# Liq_Power.net
KiCad netlist of a schematic drawn in Altium Designer
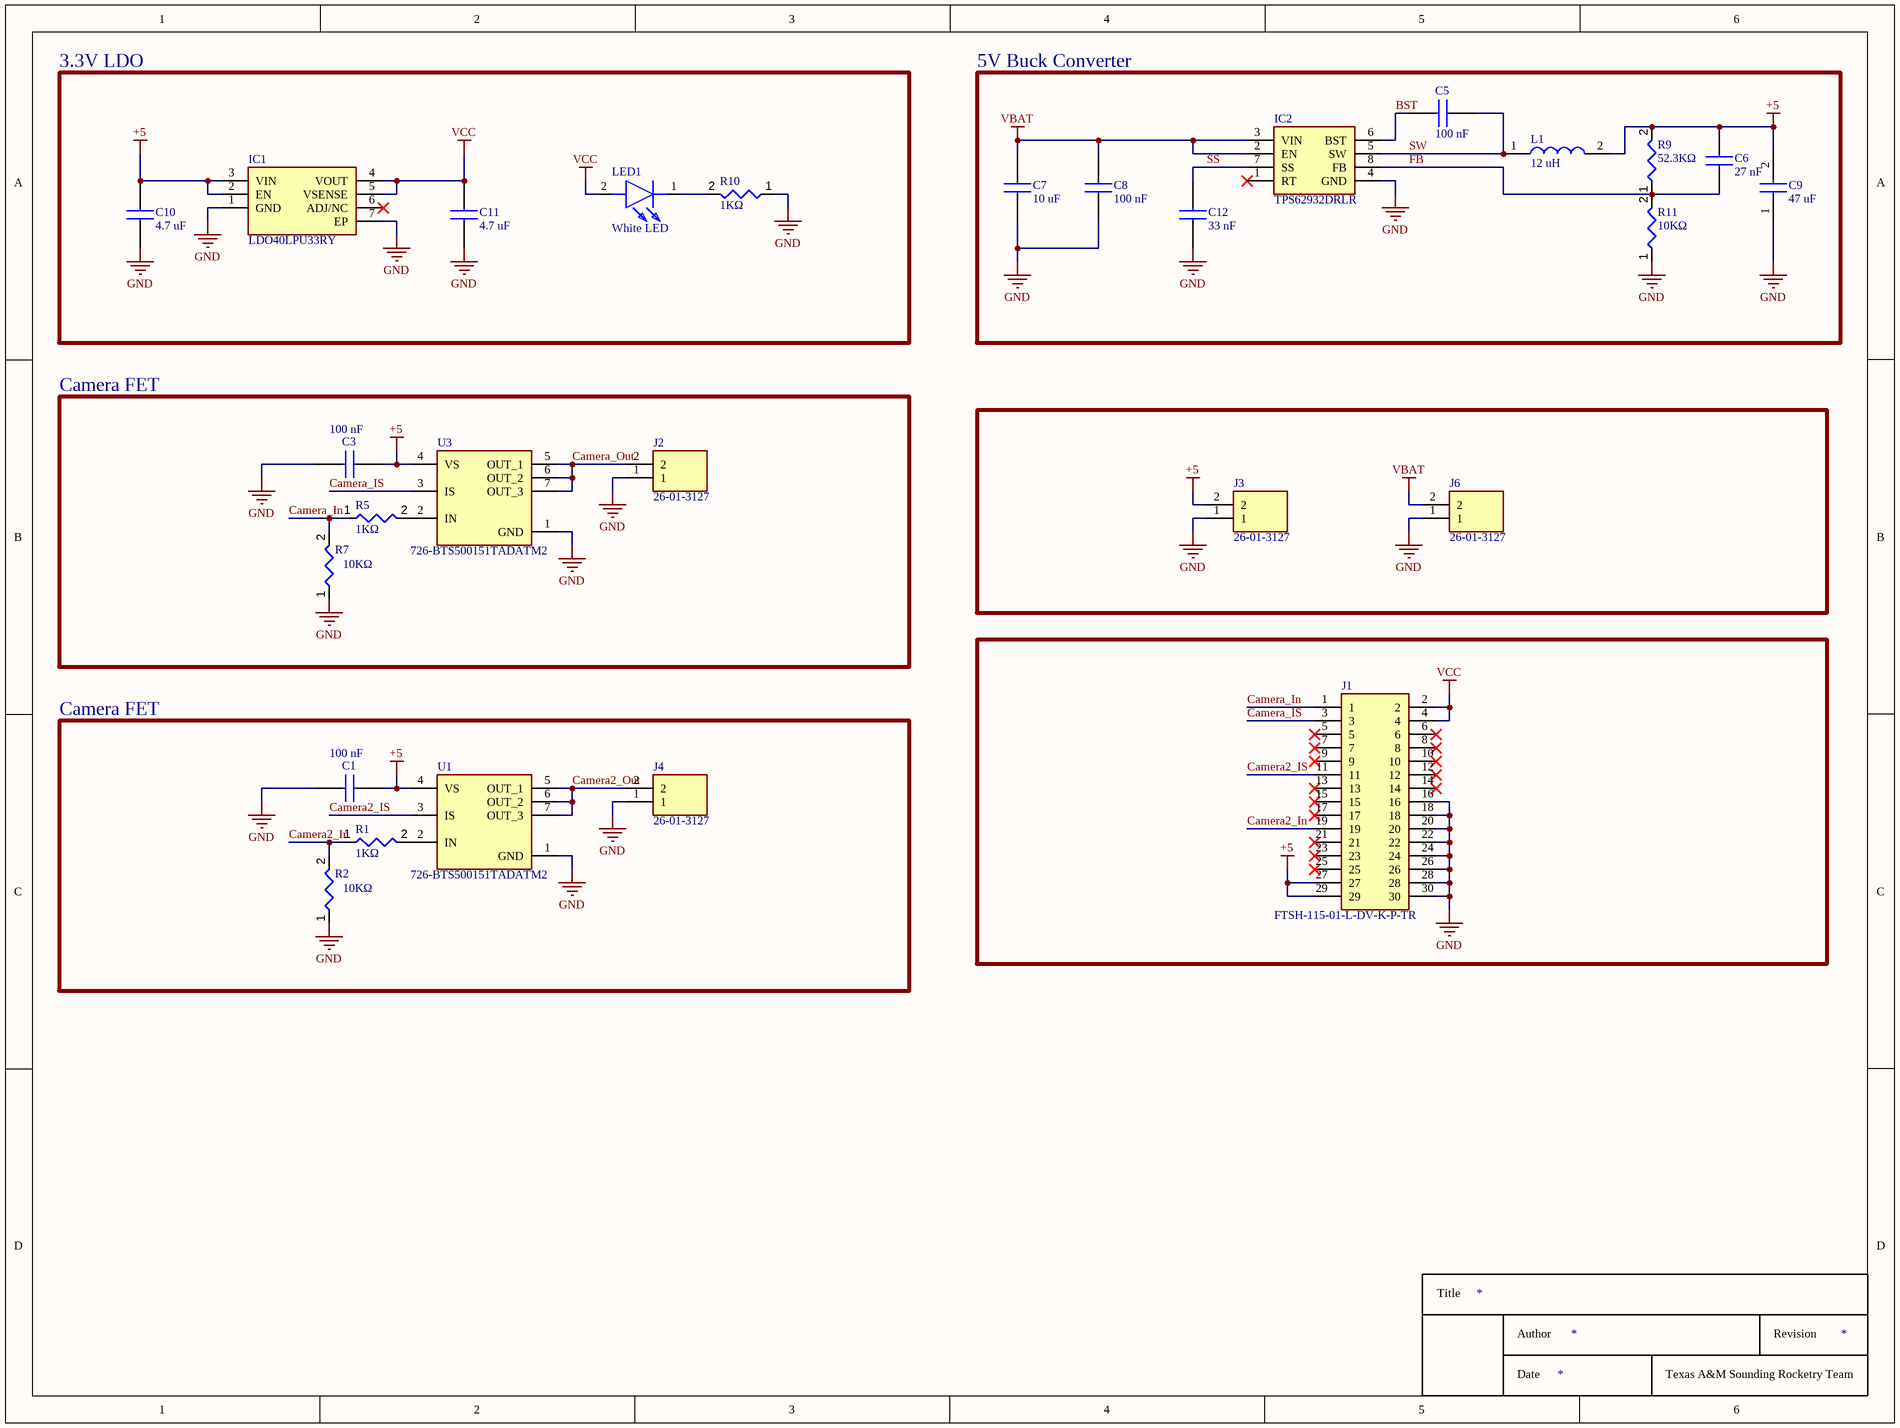
[diagram p0: Liq_Power.SchDoc]

(export (version "E")
  (design (tool "Eeschema 10.0.6"))
  (components
    (comp (ref "C1")
      (value "100 nF")
      (footprint "CAP_0603")
      (fields (field (name "TOLERANCE") "5%") (field (name "VOLTAGE") "50 V"))
      (libsource (lib "Capacitors") (part "Capacitor_BASE"))
    )
    (comp (ref "C3")
      (value "100 nF")
      (footprint "CAP_0603")
      (fields (field (name "TOLERANCE") "5%") (field (name "VOLTAGE") "50 V"))
      (libsource (lib "Capacitors") (part "Capacitor_BASE"))
    )
    (comp (ref "C5")
      (value "100 nF")
      (footprint "CAP_0603")
      (fields (field (name "TOLERANCE") "5%") (field (name "VOLTAGE") "50 V"))
      (libsource (lib "Capacitors") (part "Capacitor_BASE"))
    )
    (comp (ref "C6")
      (value "27 nF")
      (footprint "CAP_0603")
      (fields
        (field (name "TOLERANCE") "5%")
        (field (name "VOLTAGE") "50 V")
        (field (name "MPN") "581-06035C273JAT2A")
      )
      (libsource (lib "Capacitors") (part "Capacitor_BASE"))
    )
    (comp (ref "C7")
      (value "10 uF")
      (footprint "CAP_0603")
      (fields (field (name "TOLERANCE") "10%") (field (name "VOLTAGE") "25 V"))
      (libsource (lib "Capacitors") (part "Capacitor_BASE"))
    )
    (comp (ref "C8")
      (value "100 nF")
      (footprint "CAP_0603")
      (fields (field (name "TOLERANCE") "5%") (field (name "VOLTAGE") "50 V"))
      (libsource (lib "Capacitors") (part "Capacitor_BASE"))
    )
    (comp (ref "C9")
      (value "47 uF")
      (footprint "Capacitors:CAPC2012X145N")
      (description "KGM21AR51A476MU\r\n20% 10V")
      (fields
        (field (name "MANUFACTURER_PART_NUMBER") "KGM21AR51A476MU")
        (field (name "MOUSER PART NUMBER") "581-KGM21AR51A476MU")
      )
      (libsource (lib "Capacitors") (part "47 uF"))
    )
    (comp (ref "C10")
      (value "4.7 uF")
      (footprint "CAP_0603")
      (fields
        (field (name "TOLERANCE") "10%")
        (field (name "VOLTAGE") "25 V")
        (field (name "MPN") "581-06033D475KAT2A")
      )
      (libsource (lib "Capacitors") (part "Capacitor_BASE"))
    )
    (comp (ref "C11")
      (value "4.7 uF")
      (footprint "CAP_0603")
      (fields
        (field (name "TOLERANCE") "10%")
        (field (name "VOLTAGE") "25 V")
        (field (name "MPN") "581-06033D475KAT2A")
      )
      (libsource (lib "Capacitors") (part "Capacitor_BASE"))
    )
    (comp (ref "C12")
      (value "33 nF")
      (footprint "CAP_0603")
      (fields (field (name "TOLERANCE") "5%") (field (name "VOLTAGE") "50 V"))
      (libsource (lib "Capacitors") (part "Capacitor_BASE"))
    )
    (comp (ref "IC1")
      (value "LDO40LPU33RY")
      (footprint "Miscellaneous:SON95P300X300X90-7N-D")
      (description "3.3V 400 mA LDO")
      (fields (field (name "MOUSER PART NUMBER") "511-LDO40LPU33RY"))
      (libsource (lib "Miscellaneous") (part "LDO40LPU33RY"))
    )
    (comp (ref "IC2")
      (value "TPS62932DRLR")
      (footprint "Miscellaneous:TPS62932DRLR")
      (description "Integrated Circuit")
      (fields (field (name "MOUSER PART NUMBER") "595-TPS62932DRLR"))
      (libsource (lib "Miscellaneous") (part "TPS62932DRLR"))
    )
    (comp (ref "J1")
      (value "FTSH-115-01-L-DV-K-P-TR")
      (footprint "Connectors:FTSH-115-XX-YYY-DV-K-P-TR")
      (description "2x15 Board to Board")
      (fields (field (name "MOUSER PART NUMBER") "200-FTSH11501LDVKPTR"))
      (libsource (lib "Connectors") (part "FTSH-115-01-L-DV-K-P-TR"))
    )
    (comp (ref "J2")
      (value "26-01-3127")
      (footprint "SamacSys:26013127")
      (description "Connector")
      (fields (field (name "MOUSER PART NUMBER") "538-26-01-3127"))
      (libsource (lib "*") (part "26-01-3127"))
    )
    (comp (ref "J3")
      (value "26-01-3127")
      (footprint "SamacSys:26013127")
      (description "Connector")
      (fields (field (name "MOUSER PART NUMBER") "538-26-01-3127"))
      (libsource (lib "*") (part "26-01-3127"))
    )
    (comp (ref "J4")
      (value "26-01-3127")
      (footprint "SamacSys:26013127")
      (description "Connector")
      (fields (field (name "MOUSER PART NUMBER") "538-26-01-3127"))
      (libsource (lib "*") (part "26-01-3127"))
    )
    (comp (ref "J6")
      (value "26-01-3127")
      (footprint "SamacSys:26013127")
      (description "Connector")
      (fields (field (name "MOUSER PART NUMBER") "538-26-01-3127"))
      (libsource (lib "*") (part "26-01-3127"))
    )
    (comp (ref "L1")
      (value "12 uH")
      (footprint "Inductors:INDPM127127X850N")
      (description "SRR1208-120ML\r\n25 mOhm 20%")
      (fields
        (field (name "MANUFACTURER_PART_NUMBER") "SRR1208-120ML")
        (field (name "MOUSER PART NUMBER") "652-SRR1208-120ML")
      )
      (libsource (lib "Inductors") (part "12 uH"))
    )
    (comp (ref "LED1")
      (value "White LED")
      (footprint "Diodes:LEDC2012X90N")
      (description "LED")
      (fields
        (field (name "MANUFACTURER_PART_NUMBER") "HSMW-C170-U0000")
        (field (name "MPN") "630-HSMW-C170-U0000")
      )
      (libsource (lib "Diodes") (part "White LED"))
    )
    (comp (ref "R1")
      (value "1KΩ")
      (footprint "RES_0603")
      (description "Thick Film Resistors - SMD General Purpose Chip Resistor 0603, 1kOhms, 1%, 1/10W")
      (fields (field (name "TOLERANCE") "0.01") (field (name "POWER") "0.1W"))
      (libsource (lib "Resistors") (part "Resistor_BASE"))
    )
    (comp (ref "R2")
      (value "10KΩ")
      (footprint "RES_0603")
      (description "Thick Film Resistors - SMD General Purpose Chip Resistor 0603, 10kOhms, 1%, 1/10W")
      (fields (field (name "TOLERANCE") "0.01") (field (name "POWER") "0.1W"))
      (libsource (lib "Resistors") (part "Resistor_BASE"))
    )
    (comp (ref "R5")
      (value "1KΩ")
      (footprint "RES_0603")
      (description "Thick Film Resistors - SMD General Purpose Chip Resistor 0603, 1kOhms, 1%, 1/10W")
      (fields (field (name "TOLERANCE") "0.01") (field (name "POWER") "0.1W"))
      (libsource (lib "Resistors") (part "Resistor_BASE"))
    )
    (comp (ref "R7")
      (value "10KΩ")
      (footprint "RES_0603")
      (description "Thick Film Resistors - SMD General Purpose Chip Resistor 0603, 10kOhms, 1%, 1/10W")
      (fields (field (name "TOLERANCE") "0.01") (field (name "POWER") "0.1W"))
      (libsource (lib "Resistors") (part "Resistor_BASE"))
    )
    (comp (ref "R9")
      (value "52.3KΩ")
      (footprint "RES_0603")
      (description "Thick Film Resistors - SMD General Purpose Chip Resistor 0603, 52.3kOhms, 1%, 1/10W")
      (fields (field (name "TOLERANCE") "0.01") (field (name "POWER") "0.1W"))
      (libsource (lib "Resistors") (part "Resistor_BASE"))
    )
    (comp (ref "R10")
      (value "1KΩ")
      (footprint "RES_0603")
      (description "Thick Film Resistors - SMD General Purpose Chip Resistor 0603, 1kOhms, 1%, 1/10W")
      (fields (field (name "TOLERANCE") "0.01") (field (name "POWER") "0.1W"))
      (libsource (lib "Resistors") (part "Resistor_BASE"))
    )
    (comp (ref "R11")
      (value "10KΩ")
      (footprint "RES_0603")
      (description "Thick Film Resistors - SMD General Purpose Chip Resistor 0603, 10kOhms, 1%, 1/10W")
      (fields (field (name "TOLERANCE") "0.01") (field (name "POWER") "0.1W"))
      (libsource (lib "Resistors") (part "Resistor_BASE"))
    )
    (comp (ref "U1")
      (value "726-BTS500151TADATM2")
      (footprint "Transistors:BTS500151TADATMA2")
      (description "High-Side Switch 33 A")
      (fields
        (field (name "MANUFACTURER") "Infineon Technologies")
        (field (name "MANUFACTURER PART NUMBER") "BTS500151TADATMA2")
      )
      (libsource (lib "Transistors") (part "BTS500151TADATMA2"))
    )
    (comp (ref "U3")
      (value "726-BTS500151TADATM2")
      (footprint "Transistors:BTS500151TADATMA2")
      (description "High-Side Switch 33 A")
      (fields
        (field (name "MANUFACTURER") "Infineon Technologies")
        (field (name "MANUFACTURER PART NUMBER") "BTS500151TADATMA2")
      )
      (libsource (lib "Transistors") (part "BTS500151TADATMA2"))
    )
  )
  (nets
    (net (code "1") (name "+5") (class "Default")
      (node (ref "C1") (pin "1") (pinfunction "1_1") (pintype "passive"))
      (node (ref "C10") (pin "2") (pinfunction "2_2") (pintype "passive"))
      (node (ref "C3") (pin "1") (pinfunction "1_1") (pintype "passive"))
      (node (ref "C6") (pin "2") (pinfunction "2_2") (pintype "passive"))
      (node (ref "C9") (pin "2") (pinfunction "2_2") (pintype "passive"))
      (node (ref "IC1") (pin "2") (pinfunction "EN_2") (pintype "passive"))
      (node (ref "IC1") (pin "3") (pinfunction "VIN_3") (pintype "passive"))
      (node (ref "J1") (pin "27") (pinfunction "27_27") (pintype "passive"))
      (node (ref "J1") (pin "29") (pinfunction "29_29") (pintype "passive"))
      (node (ref "J3") (pin "2") (pinfunction "2_2") (pintype "passive"))
      (node (ref "L1") (pin "2") (pinfunction "2_2") (pintype "passive"))
      (node (ref "R9") (pin "2") (pinfunction "2_2") (pintype "passive"))
      (node (ref "U1") (pin "4") (pinfunction "VS_4") (pintype "passive"))
      (node (ref "U3") (pin "4") (pinfunction "VS_4") (pintype "passive"))
    )
    (net (code "2") (name "/BST") (class "Default")
      (node (ref "C5") (pin "1") (pinfunction "1_1") (pintype "passive"))
      (node (ref "IC2") (pin "6") (pinfunction "BST_6") (pintype "passive"))
    )
    (net (code "3") (name "/Camera2_IS") (class "Default")
      (node (ref "J1") (pin "11") (pinfunction "11_11") (pintype "passive"))
      (node (ref "U1") (pin "3") (pinfunction "IS_3") (pintype "passive"))
    )
    (net (code "4") (name "/Camera2_In") (class "Default")
      (node (ref "J1") (pin "19") (pinfunction "19_19") (pintype "passive"))
      (node (ref "R1") (pin "1") (pinfunction "1_1") (pintype "passive"))
      (node (ref "R2") (pin "2") (pinfunction "2_2") (pintype "passive"))
    )
    (net (code "5") (name "/Camera2_Out") (class "Default")
      (node (ref "J4") (pin "2") (pinfunction "2_2") (pintype "passive"))
      (node (ref "U1") (pin "5") (pinfunction "OUT_1_5") (pintype "passive"))
      (node (ref "U1") (pin "6") (pinfunction "OUT_2_6") (pintype "passive"))
      (node (ref "U1") (pin "7") (pinfunction "OUT_3_7") (pintype "passive"))
    )
    (net (code "6") (name "/Camera_IS") (class "Default")
      (node (ref "J1") (pin "3") (pinfunction "3_3") (pintype "passive"))
      (node (ref "U3") (pin "3") (pinfunction "IS_3") (pintype "passive"))
    )
    (net (code "7") (name "/Camera_In") (class "Default")
      (node (ref "J1") (pin "1") (pinfunction "1_1") (pintype "passive"))
      (node (ref "R5") (pin "1") (pinfunction "1_1") (pintype "passive"))
      (node (ref "R7") (pin "2") (pinfunction "2_2") (pintype "passive"))
    )
    (net (code "8") (name "/Camera_Out") (class "Default")
      (node (ref "J2") (pin "2") (pinfunction "2_2") (pintype "passive"))
      (node (ref "U3") (pin "5") (pinfunction "OUT_1_5") (pintype "passive"))
      (node (ref "U3") (pin "6") (pinfunction "OUT_2_6") (pintype "passive"))
      (node (ref "U3") (pin "7") (pinfunction "OUT_3_7") (pintype "passive"))
    )
    (net (code "9") (name "/FB") (class "Default")
      (node (ref "C6") (pin "1") (pinfunction "1_1") (pintype "passive"))
      (node (ref "IC2") (pin "8") (pinfunction "FB_8") (pintype "passive"))
      (node (ref "R11") (pin "2") (pinfunction "2_2") (pintype "passive"))
      (node (ref "R9") (pin "1") (pinfunction "1_1") (pintype "passive"))
    )
    (net (code "10") (name "/SS") (class "Default")
      (node (ref "C12") (pin "2") (pinfunction "2_2") (pintype "passive"))
      (node (ref "IC2") (pin "7") (pinfunction "SS_7") (pintype "passive"))
    )
    (net (code "11") (name "/SW") (class "Default")
      (node (ref "C5") (pin "2") (pinfunction "2_2") (pintype "passive"))
      (node (ref "IC2") (pin "5") (pinfunction "SW_5") (pintype "passive"))
      (node (ref "L1") (pin "1") (pinfunction "1_1") (pintype "passive"))
    )
    (net (code "12") (name "GND") (class "Default")
      (node (ref "C1") (pin "2") (pinfunction "2_2") (pintype "passive"))
      (node (ref "C10") (pin "1") (pinfunction "1_1") (pintype "passive"))
      (node (ref "C11") (pin "1") (pinfunction "1_1") (pintype "passive"))
      (node (ref "C12") (pin "1") (pinfunction "1_1") (pintype "passive"))
      (node (ref "C3") (pin "2") (pinfunction "2_2") (pintype "passive"))
      (node (ref "C7") (pin "1") (pinfunction "1_1") (pintype "passive"))
      (node (ref "C8") (pin "1") (pinfunction "1_1") (pintype "passive"))
      (node (ref "C9") (pin "1") (pinfunction "1_1") (pintype "passive"))
      (node (ref "IC1") (pin "1") (pinfunction "GND_1") (pintype "passive"))
      (node (ref "IC1") (pin "7") (pinfunction "EP_7") (pintype "passive"))
      (node (ref "IC2") (pin "4") (pinfunction "GND_4") (pintype "passive"))
      (node (ref "J1") (pin "16") (pinfunction "16_16") (pintype "passive"))
      (node (ref "J1") (pin "18") (pinfunction "18_18") (pintype "passive"))
      (node (ref "J1") (pin "20") (pinfunction "20_20") (pintype "passive"))
      (node (ref "J1") (pin "22") (pinfunction "22_22") (pintype "passive"))
      (node (ref "J1") (pin "24") (pinfunction "24_24") (pintype "passive"))
      (node (ref "J1") (pin "26") (pinfunction "26_26") (pintype "passive"))
      (node (ref "J1") (pin "28") (pinfunction "28_28") (pintype "passive"))
      (node (ref "J1") (pin "30") (pinfunction "30_30") (pintype "passive"))
      (node (ref "J2") (pin "1") (pinfunction "1_1") (pintype "passive"))
      (node (ref "J3") (pin "1") (pinfunction "1_1") (pintype "passive"))
      (node (ref "J4") (pin "1") (pinfunction "1_1") (pintype "passive"))
      (node (ref "J6") (pin "1") (pinfunction "1_1") (pintype "passive"))
      (node (ref "R10") (pin "1") (pinfunction "1_1") (pintype "passive"))
      (node (ref "R11") (pin "1") (pinfunction "1_1") (pintype "passive"))
      (node (ref "R2") (pin "1") (pinfunction "1_1") (pintype "passive"))
      (node (ref "R7") (pin "1") (pinfunction "1_1") (pintype "passive"))
      (node (ref "U1") (pin "1") (pinfunction "GND_1") (pintype "passive"))
      (node (ref "U3") (pin "1") (pinfunction "GND_1") (pintype "passive"))
    )
    (net (code "13") (name "Net-(LED1-K)") (class "Default")
      (node (ref "LED1") (pin "1") (pinfunction "K_1") (pintype "passive"))
      (node (ref "R10") (pin "2") (pinfunction "2_2") (pintype "passive"))
    )
    (net (code "14") (name "Net-(U1-IN)") (class "Default")
      (node (ref "R1") (pin "2") (pinfunction "2_2") (pintype "passive"))
      (node (ref "U1") (pin "2") (pinfunction "IN_2") (pintype "passive"))
    )
    (net (code "15") (name "Net-(U3-IN)") (class "Default")
      (node (ref "R5") (pin "2") (pinfunction "2_2") (pintype "passive"))
      (node (ref "U3") (pin "2") (pinfunction "IN_2") (pintype "passive"))
    )
    (net (code "16") (name "VBAT") (class "Default")
      (node (ref "C7") (pin "2") (pinfunction "2_2") (pintype "passive"))
      (node (ref "C8") (pin "2") (pinfunction "2_2") (pintype "passive"))
      (node (ref "IC2") (pin "2") (pinfunction "EN_2") (pintype "passive"))
      (node (ref "IC2") (pin "3") (pinfunction "VIN_3") (pintype "passive"))
      (node (ref "J6") (pin "2") (pinfunction "2_2") (pintype "passive"))
    )
    (net (code "17") (name "VCC") (class "Default")
      (node (ref "C11") (pin "2") (pinfunction "2_2") (pintype "passive"))
      (node (ref "IC1") (pin "4") (pinfunction "VOUT_4") (pintype "passive"))
      (node (ref "IC1") (pin "5") (pinfunction "VSENSE_5") (pintype "passive"))
      (node (ref "J1") (pin "2") (pinfunction "2_2") (pintype "passive"))
      (node (ref "J1") (pin "4") (pinfunction "4_4") (pintype "passive"))
      (node (ref "LED1") (pin "2") (pinfunction "A_2") (pintype "passive"))
    )
    (net (code "18") (name "unconnected-(IC1-ADJ{slash}NC-Pad6)") (class "Default")
      (node (ref "IC1") (pin "6") (pinfunction "ADJ/NC_6") (pintype "passive+no_connect"))
    )
    (net (code "19") (name "unconnected-(IC2-RT-Pad1)") (class "Default")
      (node (ref "IC2") (pin "1") (pinfunction "RT_1") (pintype "passive+no_connect"))
    )
    (net (code "20") (name "unconnected-(J1-Pad5)") (class "Default")
      (node (ref "J1") (pin "5") (pinfunction "5_5") (pintype "passive+no_connect"))
    )
    (net (code "21") (name "unconnected-(J1-Pad6)") (class "Default")
      (node (ref "J1") (pin "6") (pinfunction "6_6") (pintype "passive+no_connect"))
    )
    (net (code "22") (name "unconnected-(J1-Pad7)") (class "Default")
      (node (ref "J1") (pin "7") (pinfunction "7_7") (pintype "passive+no_connect"))
    )
    (net (code "23") (name "unconnected-(J1-Pad8)") (class "Default")
      (node (ref "J1") (pin "8") (pinfunction "8_8") (pintype "passive+no_connect"))
    )
    (net (code "24") (name "unconnected-(J1-Pad9)") (class "Default")
      (node (ref "J1") (pin "9") (pinfunction "9_9") (pintype "passive+no_connect"))
    )
    (net (code "25") (name "unconnected-(J1-Pad10)") (class "Default")
      (node (ref "J1") (pin "10") (pinfunction "10_10") (pintype "passive+no_connect"))
    )
    (net (code "26") (name "unconnected-(J1-Pad12)") (class "Default")
      (node (ref "J1") (pin "12") (pinfunction "12_12") (pintype "passive+no_connect"))
    )
    (net (code "27") (name "unconnected-(J1-Pad13)") (class "Default")
      (node (ref "J1") (pin "13") (pinfunction "13_13") (pintype "passive+no_connect"))
    )
    (net (code "28") (name "unconnected-(J1-Pad14)") (class "Default")
      (node (ref "J1") (pin "14") (pinfunction "14_14") (pintype "passive+no_connect"))
    )
    (net (code "29") (name "unconnected-(J1-Pad15)") (class "Default")
      (node (ref "J1") (pin "15") (pinfunction "15_15") (pintype "passive+no_connect"))
    )
    (net (code "30") (name "unconnected-(J1-Pad17)") (class "Default")
      (node (ref "J1") (pin "17") (pinfunction "17_17") (pintype "passive+no_connect"))
    )
    (net (code "31") (name "unconnected-(J1-Pad21)") (class "Default")
      (node (ref "J1") (pin "21") (pinfunction "21_21") (pintype "passive+no_connect"))
    )
    (net (code "32") (name "unconnected-(J1-Pad23)") (class "Default")
      (node (ref "J1") (pin "23") (pinfunction "23_23") (pintype "passive+no_connect"))
    )
    (net (code "33") (name "unconnected-(J1-Pad25)") (class "Default")
      (node (ref "J1") (pin "25") (pinfunction "25_25") (pintype "passive+no_connect"))
    )
  )
)
